# LoRaBaseStation.net
KiCad netlist of a schematic drawn in Altium Designer
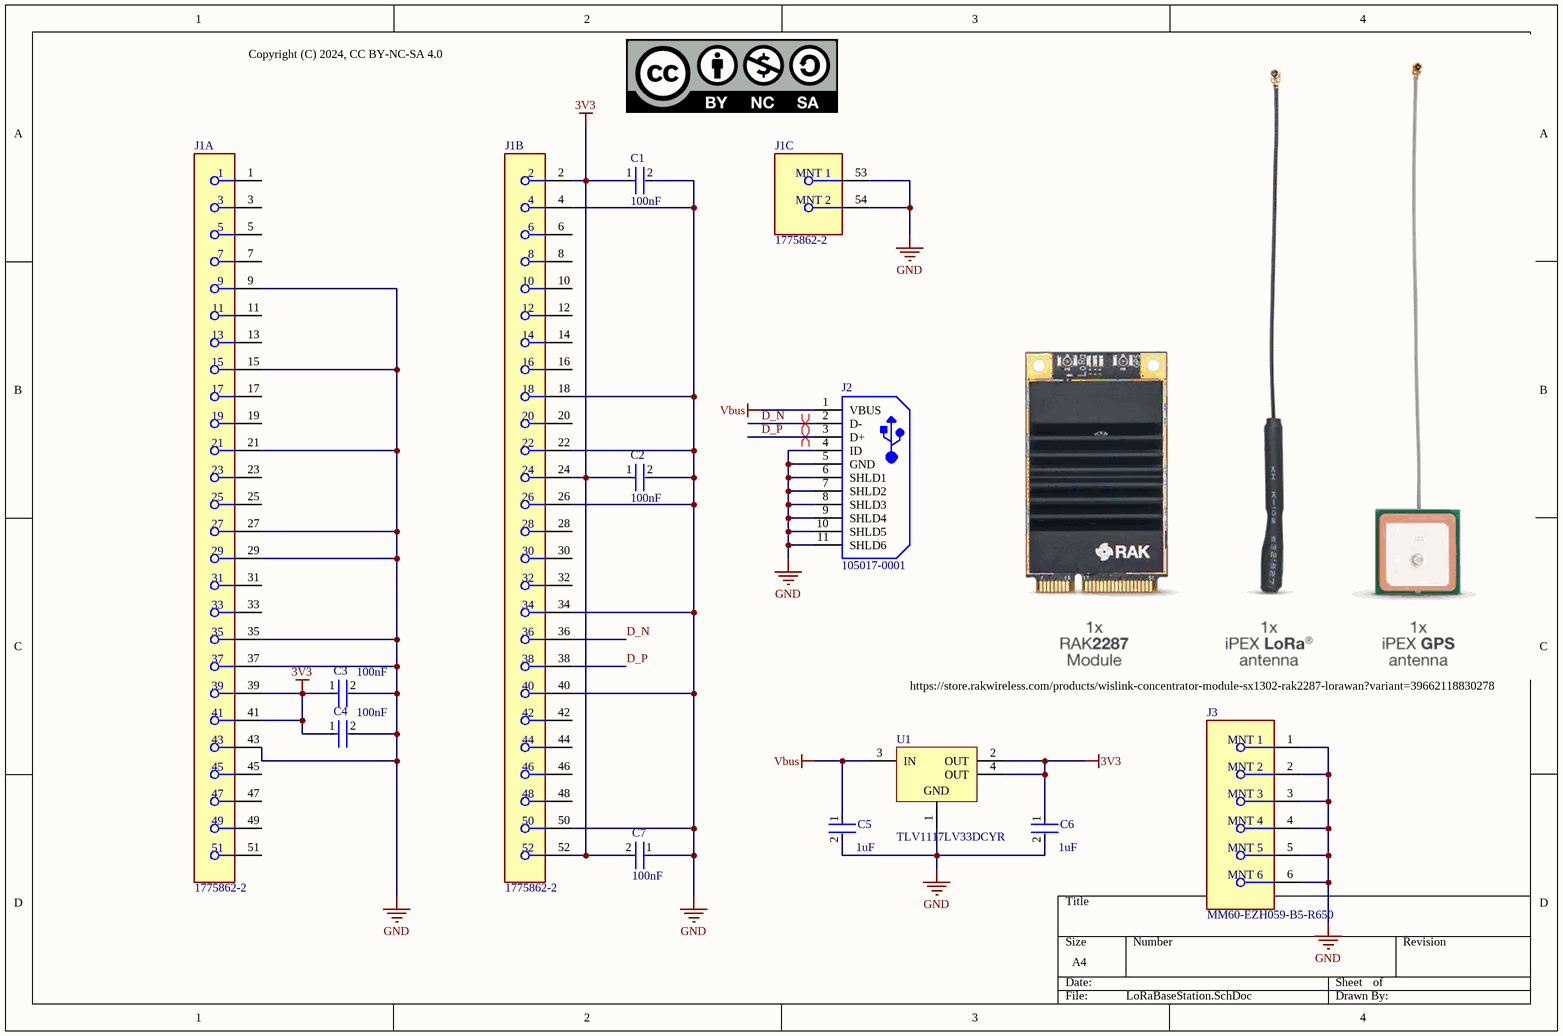
[diagram p0: LoRaBaseStation.SchDoc]

(export (version "E")
  (design (tool "Eeschema 10.0.6"))
  (components
    (comp (ref "C1")
      (value "GRM155R71E104KE14J")
      (footprint "FP-GRM155-0_05-IPC_C")
      (description "Chip Multilayer Ceramic Capacitors for General Purpose, 0402, 0.10uF, X7R, 15%, 10%, 25V")
      (fields (field (name "CAPACITANCE") "100nF") (field (name "TOLERANCE") "10%"))
      (libsource (lib "Altium Content Vault") (part "02cd4be3c70576c341d710602a673aa"))
    )
    (comp (ref "C2")
      (value "GRM155R71E104KE14J")
      (footprint "FP-GRM155-0_05-IPC_C")
      (description "Chip Multilayer Ceramic Capacitors for General Purpose, 0402, 0.10uF, X7R, 15%, 10%, 25V")
      (fields (field (name "CAPACITANCE") "100nF") (field (name "TOLERANCE") "10%"))
      (libsource (lib "Altium Content Vault") (part "02cd4be3c70576c341d710602a673aa"))
    )
    (comp (ref "C3")
      (value "GRM155R71E104KE14J")
      (footprint "FP-GRM155-0_05-IPC_C")
      (description "Chip Multilayer Ceramic Capacitors for General Purpose, 0402, 0.10uF, X7R, 15%, 10%, 25V")
      (fields (field (name "CAPACITANCE") "100nF") (field (name "TOLERANCE") "10%"))
      (libsource (lib "Altium Content Vault") (part "02cd4be3c70576c341d710602a673aa"))
    )
    (comp (ref "C4")
      (value "GRM155R71E104KE14J")
      (footprint "FP-GRM155-0_05-IPC_C")
      (description "Chip Multilayer Ceramic Capacitors for General Purpose, 0402, 0.10uF, X7R, 15%, 10%, 25V")
      (fields (field (name "CAPACITANCE") "100nF") (field (name "TOLERANCE") "10%"))
      (libsource (lib "Altium Content Vault") (part "02cd4be3c70576c341d710602a673aa"))
    )
    (comp (ref "C5")
      (value "CL05A105KP5NNNC")
      (footprint "FP-CL511-IPC_C")
      (description "Cap Ceramic 1uF 10V X5R ±10% SMD 0402 +85°C Paper T/R")
      (fields (field (name "CAPACITANCE") "1uF") (field (name "TOLERANCE") "10%"))
      (libsource (lib "Altium Content Vault") (part "b4654b650e69147ec39a6b967a45e02"))
    )
    (comp (ref "C6")
      (value "CL05A105KP5NNNC")
      (footprint "FP-CL511-IPC_C")
      (description "Cap Ceramic 1uF 10V X5R ±10% SMD 0402 +85°C Paper T/R")
      (fields (field (name "CAPACITANCE") "1uF") (field (name "TOLERANCE") "10%"))
      (libsource (lib "Altium Content Vault") (part "b4654b650e69147ec39a6b967a45e02"))
    )
    (comp (ref "C7")
      (value "GRM155R71E104KE14J")
      (footprint "FP-GRM155-0_05-IPC_C")
      (description "Chip Multilayer Ceramic Capacitors for General Purpose, 0402, 0.10uF, X7R, 15%, 10%, 25V")
      (fields (field (name "CAPACITANCE") "100nF") (field (name "TOLERANCE") "10%"))
      (libsource (lib "Altium Content Vault") (part "02cd4be3c70576c341d710602a673aa"))
    )
    (comp (ref "J1")
      (value "1775862-2")
      (footprint "FP-1775862-2-MFG")
      (description "CONN PCI EXP MINI FEMALE 52POS")
      (libsource (lib "Altium Content Vault") (part "f6f1911ae65d5f648a4edbf75ba42ef"))
    )
    (comp (ref "J2")
      (value "105017-0001")
      (footprint "USB-MICRO-B_V")
      (fields (field (name "MANUFACTURER") "Molex"))
      (libsource (lib "Altium Content Vault") (part "USB-5-6SHLD"))
    )
    (comp (ref "J3")
      (value "MM60-EZH059-B5-R650")
      (footprint "FP-MM60-EZH059-B5-R650-MFG")
      (description "CONN MINI EXPRESS CARD LATCH SMD")
      (libsource (lib "Altium Content Vault") (part "7a3d3201a7a8e9cb9455949333560c2"))
    )
    (comp (ref "U1")
      (value "TLV1117LV33DCYR")
      (footprint "DCY0004A_N")
      (fields (field (name "MANUFACTURER") "Texas Instruments"))
      (libsource (lib "Altium Content Vault") (part "TI-TLV1117LV33DCY4"))
    )
  )
  (nets
    (net (code "1") (name "/D_N") (class "Default")
      (node (ref "J1") (pin "36") (pinfunction "36_36") (pintype "passive"))
      (node (ref "J2") (pin "2") (pinfunction "D-_2") (pintype "passive"))
    )
    (net (code "2") (name "/D_P") (class "Default")
      (node (ref "J1") (pin "38") (pinfunction "38_38") (pintype "passive"))
      (node (ref "J2") (pin "3") (pinfunction "D+_3") (pintype "passive"))
    )
    (net (code "3") (name "3V3") (class "Default")
      (node (ref "C1") (pin "1") (pinfunction "1_1") (pintype "passive"))
      (node (ref "C2") (pin "1") (pinfunction "1_1") (pintype "passive"))
      (node (ref "C3") (pin "1") (pinfunction "1_1") (pintype "passive"))
      (node (ref "C4") (pin "1") (pinfunction "1_1") (pintype "passive"))
      (node (ref "C6") (pin "1") (pinfunction "1_1") (pintype "passive"))
      (node (ref "C7") (pin "2") (pinfunction "2_2") (pintype "passive"))
      (node (ref "J1") (pin "2") (pinfunction "2_2") (pintype "passive"))
      (node (ref "J1") (pin "24") (pinfunction "24_24") (pintype "passive"))
      (node (ref "J1") (pin "39") (pinfunction "39_39") (pintype "passive"))
      (node (ref "J1") (pin "41") (pinfunction "41_41") (pintype "passive"))
      (node (ref "J1") (pin "52") (pinfunction "52_52") (pintype "passive"))
      (node (ref "U1") (pin "2") (pinfunction "OUT_2") (pintype "power_in"))
      (node (ref "U1") (pin "4") (pinfunction "OUT_4") (pintype "power_in"))
    )
    (net (code "4") (name "GND") (class "Default")
      (node (ref "C1") (pin "2") (pinfunction "2_2") (pintype "passive"))
      (node (ref "C2") (pin "2") (pinfunction "2_2") (pintype "passive"))
      (node (ref "C3") (pin "2") (pinfunction "2_2") (pintype "passive"))
      (node (ref "C4") (pin "2") (pinfunction "2_2") (pintype "passive"))
      (node (ref "C5") (pin "2") (pinfunction "2_2") (pintype "passive"))
      (node (ref "C6") (pin "2") (pinfunction "2_2") (pintype "passive"))
      (node (ref "C7") (pin "1") (pinfunction "1_1") (pintype "passive"))
      (node (ref "J1") (pin "15") (pinfunction "15_15") (pintype "passive"))
      (node (ref "J1") (pin "18") (pinfunction "18_18") (pintype "passive"))
      (node (ref "J1") (pin "21") (pinfunction "21_21") (pintype "passive"))
      (node (ref "J1") (pin "22") (pinfunction "22_22") (pintype "passive"))
      (node (ref "J1") (pin "26") (pinfunction "26_26") (pintype "passive"))
      (node (ref "J1") (pin "27") (pinfunction "27_27") (pintype "passive"))
      (node (ref "J1") (pin "29") (pinfunction "29_29") (pintype "passive"))
      (node (ref "J1") (pin "34") (pinfunction "34_34") (pintype "passive"))
      (node (ref "J1") (pin "35") (pinfunction "35_35") (pintype "passive"))
      (node (ref "J1") (pin "37") (pinfunction "37_37") (pintype "passive"))
      (node (ref "J1") (pin "4") (pinfunction "4_4") (pintype "passive"))
      (node (ref "J1") (pin "40") (pinfunction "40_40") (pintype "passive"))
      (node (ref "J1") (pin "43") (pinfunction "43_43") (pintype "passive"))
      (node (ref "J1") (pin "50") (pinfunction "50_50") (pintype "passive"))
      (node (ref "J1") (pin "53") (pinfunction "MNT_1_53") (pintype "passive"))
      (node (ref "J1") (pin "54") (pinfunction "MNT_2_54") (pintype "passive"))
      (node (ref "J1") (pin "9") (pinfunction "9_9") (pintype "passive"))
      (node (ref "J2") (pin "10") (pinfunction "SHLD5_10") (pintype "passive"))
      (node (ref "J2") (pin "11") (pinfunction "SHLD6_11") (pintype "passive"))
      (node (ref "J2") (pin "4") (pinfunction "ID_4") (pintype "passive"))
      (node (ref "J2") (pin "5") (pinfunction "GND_5") (pintype "passive"))
      (node (ref "J2") (pin "6") (pinfunction "SHLD1_6") (pintype "passive"))
      (node (ref "J2") (pin "7") (pinfunction "SHLD2_7") (pintype "passive"))
      (node (ref "J2") (pin "8") (pinfunction "SHLD3_8") (pintype "passive"))
      (node (ref "J2") (pin "9") (pinfunction "SHLD4_9") (pintype "passive"))
      (node (ref "J3") (pin "1") (pinfunction "MNT_1_1") (pintype "passive"))
      (node (ref "J3") (pin "2") (pinfunction "MNT_2_2") (pintype "passive"))
      (node (ref "J3") (pin "3") (pinfunction "MNT_3_3") (pintype "passive"))
      (node (ref "J3") (pin "4") (pinfunction "MNT_4_4") (pintype "passive"))
      (node (ref "J3") (pin "5") (pinfunction "MNT_5_5") (pintype "passive"))
      (node (ref "J3") (pin "6") (pinfunction "MNT_6_6") (pintype "passive"))
      (node (ref "U1") (pin "1") (pinfunction "GND_1") (pintype "power_in"))
    )
    (net (code "5") (name "Vbus") (class "Default")
      (node (ref "C5") (pin "1") (pinfunction "1_1") (pintype "passive"))
      (node (ref "J2") (pin "1") (pinfunction "VBUS_1") (pintype "passive"))
      (node (ref "U1") (pin "3") (pinfunction "IN_3") (pintype "power_in"))
    )
    (net (code "6") (name "unconnected-(J1-Pad1)") (class "Default")
      (node (ref "J1") (pin "1") (pinfunction "1_1") (pintype "passive"))
    )
    (net (code "7") (name "unconnected-(J1-Pad3)") (class "Default")
      (node (ref "J1") (pin "3") (pinfunction "3_3") (pintype "passive"))
    )
    (net (code "8") (name "unconnected-(J1-Pad5)") (class "Default")
      (node (ref "J1") (pin "5") (pinfunction "5_5") (pintype "passive"))
    )
    (net (code "9") (name "unconnected-(J1-Pad6)") (class "Default")
      (node (ref "J1") (pin "6") (pinfunction "6_6") (pintype "passive"))
    )
    (net (code "10") (name "unconnected-(J1-Pad7)") (class "Default")
      (node (ref "J1") (pin "7") (pinfunction "7_7") (pintype "passive"))
    )
    (net (code "11") (name "unconnected-(J1-Pad8)") (class "Default")
      (node (ref "J1") (pin "8") (pinfunction "8_8") (pintype "passive"))
    )
    (net (code "12") (name "unconnected-(J1-Pad10)") (class "Default")
      (node (ref "J1") (pin "10") (pinfunction "10_10") (pintype "passive"))
    )
    (net (code "13") (name "unconnected-(J1-Pad11)") (class "Default")
      (node (ref "J1") (pin "11") (pinfunction "11_11") (pintype "passive"))
    )
    (net (code "14") (name "unconnected-(J1-Pad12)") (class "Default")
      (node (ref "J1") (pin "12") (pinfunction "12_12") (pintype "passive"))
    )
    (net (code "15") (name "unconnected-(J1-Pad13)") (class "Default")
      (node (ref "J1") (pin "13") (pinfunction "13_13") (pintype "passive"))
    )
    (net (code "16") (name "unconnected-(J1-Pad14)") (class "Default")
      (node (ref "J1") (pin "14") (pinfunction "14_14") (pintype "passive"))
    )
    (net (code "17") (name "unconnected-(J1-Pad16)") (class "Default")
      (node (ref "J1") (pin "16") (pinfunction "16_16") (pintype "passive"))
    )
    (net (code "18") (name "unconnected-(J1-Pad17)") (class "Default")
      (node (ref "J1") (pin "17") (pinfunction "17_17") (pintype "passive"))
    )
    (net (code "19") (name "unconnected-(J1-Pad19)") (class "Default")
      (node (ref "J1") (pin "19") (pinfunction "19_19") (pintype "passive"))
    )
    (net (code "20") (name "unconnected-(J1-Pad20)") (class "Default")
      (node (ref "J1") (pin "20") (pinfunction "20_20") (pintype "passive"))
    )
    (net (code "21") (name "unconnected-(J1-Pad23)") (class "Default")
      (node (ref "J1") (pin "23") (pinfunction "23_23") (pintype "passive"))
    )
    (net (code "22") (name "unconnected-(J1-Pad25)") (class "Default")
      (node (ref "J1") (pin "25") (pinfunction "25_25") (pintype "passive"))
    )
    (net (code "23") (name "unconnected-(J1-Pad28)") (class "Default")
      (node (ref "J1") (pin "28") (pinfunction "28_28") (pintype "passive"))
    )
    (net (code "24") (name "unconnected-(J1-Pad30)") (class "Default")
      (node (ref "J1") (pin "30") (pinfunction "30_30") (pintype "passive"))
    )
    (net (code "25") (name "unconnected-(J1-Pad31)") (class "Default")
      (node (ref "J1") (pin "31") (pinfunction "31_31") (pintype "passive"))
    )
    (net (code "26") (name "unconnected-(J1-Pad32)") (class "Default")
      (node (ref "J1") (pin "32") (pinfunction "32_32") (pintype "passive"))
    )
    (net (code "27") (name "unconnected-(J1-Pad33)") (class "Default")
      (node (ref "J1") (pin "33") (pinfunction "33_33") (pintype "passive"))
    )
    (net (code "28") (name "unconnected-(J1-Pad42)") (class "Default")
      (node (ref "J1") (pin "42") (pinfunction "42_42") (pintype "passive"))
    )
    (net (code "29") (name "unconnected-(J1-Pad44)") (class "Default")
      (node (ref "J1") (pin "44") (pinfunction "44_44") (pintype "passive"))
    )
    (net (code "30") (name "unconnected-(J1-Pad45)") (class "Default")
      (node (ref "J1") (pin "45") (pinfunction "45_45") (pintype "passive"))
    )
    (net (code "31") (name "unconnected-(J1-Pad46)") (class "Default")
      (node (ref "J1") (pin "46") (pinfunction "46_46") (pintype "passive"))
    )
    (net (code "32") (name "unconnected-(J1-Pad47)") (class "Default")
      (node (ref "J1") (pin "47") (pinfunction "47_47") (pintype "passive"))
    )
    (net (code "33") (name "unconnected-(J1-Pad48)") (class "Default")
      (node (ref "J1") (pin "48") (pinfunction "48_48") (pintype "passive"))
    )
    (net (code "34") (name "unconnected-(J1-Pad49)") (class "Default")
      (node (ref "J1") (pin "49") (pinfunction "49_49") (pintype "passive"))
    )
    (net (code "35") (name "unconnected-(J1-Pad51)") (class "Default")
      (node (ref "J1") (pin "51") (pinfunction "51_51") (pintype "passive"))
    )
  )
)
